# USB_Serial_Quad.net
KiCad netlist of a schematic drawn in Altium Designer
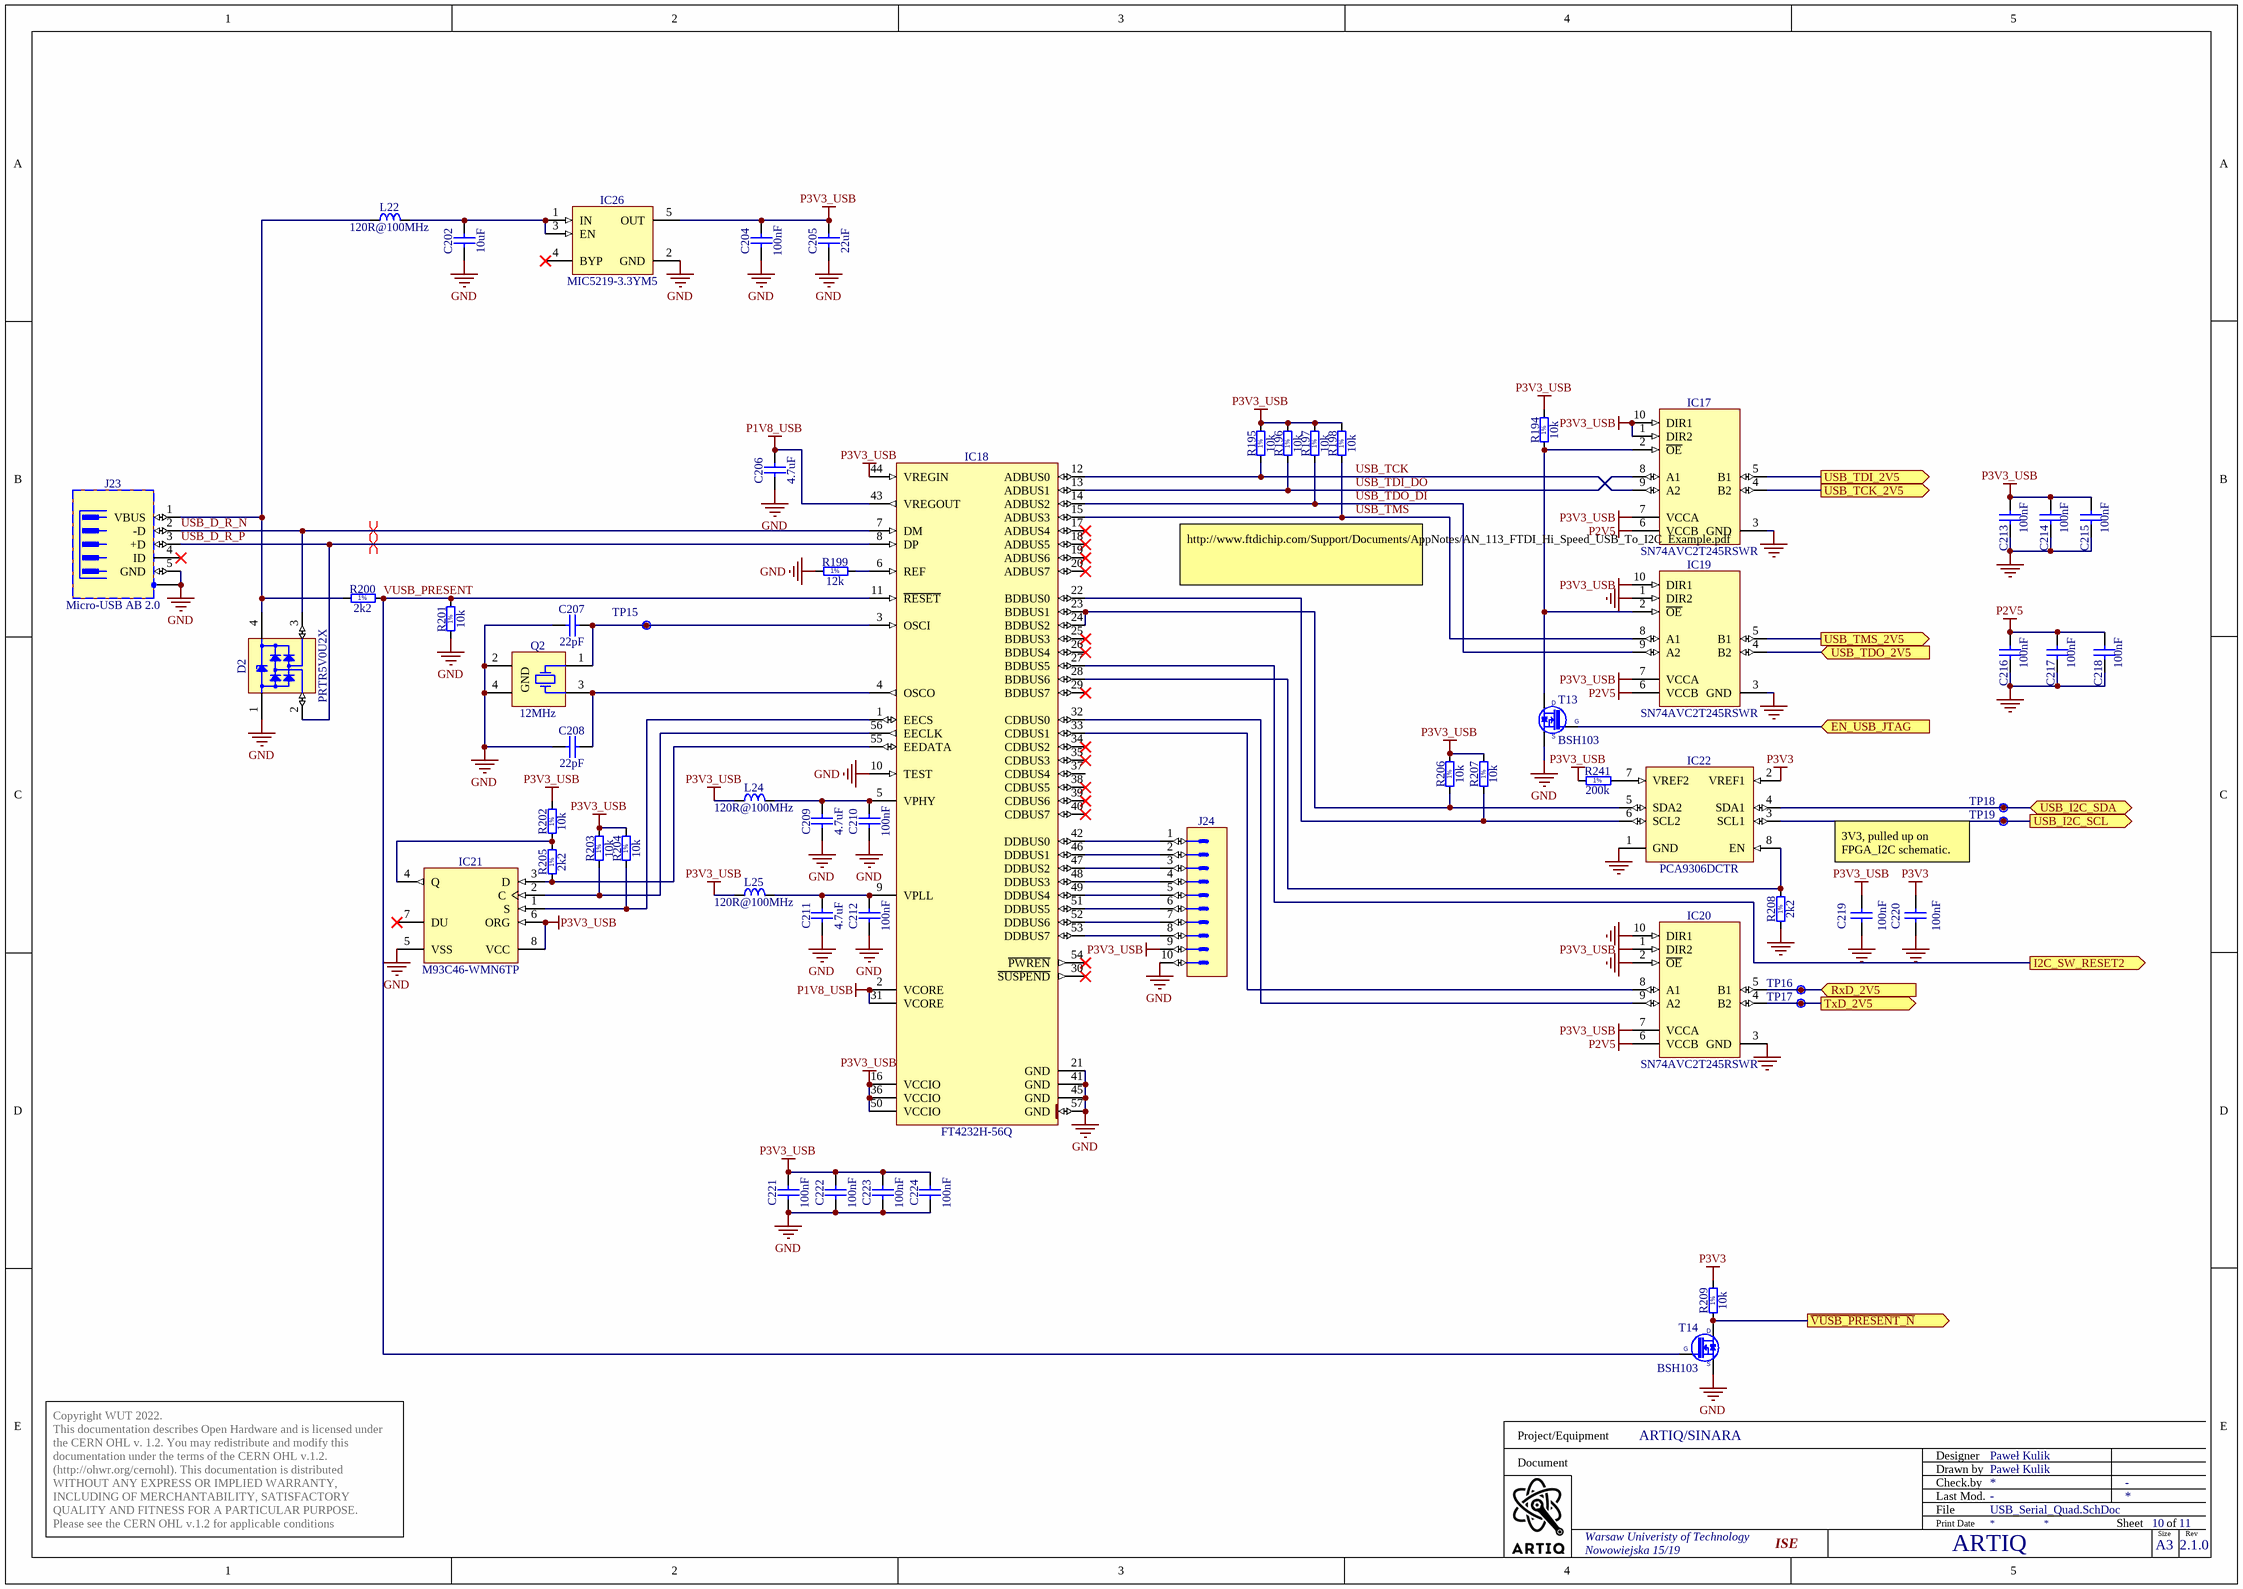
[diagram p0: USB_Serial_Quad.SchDoc]

(export (version "E")
  (design (tool "Eeschema 10.0.6"))
  (components
    (comp (ref "C202")
      (value "10uF")
      (footprint "CAPC1608X87N")
      (description "Non-polarised capacitor")
      (fields
        (field (name "PART NUMBER") "CC0603_10UF_6.3V_20%_X5R")
        (field (name "VOLTAGE") "6.3V")
        (field (name "AUTHOR") "CERN DEM JLC")
      )
      (libsource (lib "Capacitors") (part "Capacitor - non polarized"))
    )
    (comp (ref "C204")
      (value "100nF")
      (footprint "CAPC0603X33N")
      (description "Non-polarised capacitor")
      (fields
        (field (name "PART NUMBER") "CC0201_100NF_6.3V_10%_X5R")
        (field (name "VOLTAGE") "6.3V")
        (field (name "AUTHOR") "CERN DEM JLC")
      )
      (libsource (lib "Capacitors") (part "Capacitor - non polarized"))
    )
    (comp (ref "C205")
      (value "22uF")
      (footprint "CAPC1709X100N")
      (description "Non-polarised capacitor")
      (fields
        (field (name "PART NUMBER") "CC0603_22UF_6.3V_20%_X5R")
        (field (name "VOLTAGE") "6.3V")
        (field (name "AUTHOR") "CERN DEM JLC")
      )
      (libsource (lib "Capacitors") (part "Capacitor - non polarized"))
    )
    (comp (ref "C206")
      (value "4.7uF")
      (footprint "CAPC2012X135N")
      (description "Non-polarised capacitor")
      (fields
        (field (name "PART NUMBER") "CC0805_4.7UF_10V_10%_X5R")
        (field (name "VOLTAGE") "10V")
        (field (name "AUTHOR") "CERN DEM JLC")
      )
      (libsource (lib "Capacitors") (part "Capacitor - non polarized"))
    )
    (comp (ref "C207")
      (value "22pF")
      (footprint "CAPC1005X55N")
      (description "Non-polarised capacitor")
      (fields
        (field (name "PART NUMBER") "CC0402_22PF_50V_5%_C0G")
        (field (name "VOLTAGE") "50V")
        (field (name "AUTHOR") "CERN DEM JLC")
      )
      (libsource (lib "Capacitors") (part "Capacitor - non polarized"))
    )
    (comp (ref "C208")
      (value "22pF")
      (footprint "CAPC1005X55N")
      (description "Non-polarised capacitor")
      (fields
        (field (name "PART NUMBER") "CC0402_22PF_50V_5%_C0G")
        (field (name "VOLTAGE") "50V")
        (field (name "AUTHOR") "CERN DEM JLC")
      )
      (libsource (lib "Capacitors") (part "Capacitor - non polarized"))
    )
    (comp (ref "C209")
      (value "4.7uF")
      (footprint "CAPC2012X135N")
      (description "Non-polarised capacitor")
      (fields
        (field (name "PART NUMBER") "CC0805_4.7UF_10V_10%_X5R")
        (field (name "VOLTAGE") "10V")
        (field (name "AUTHOR") "CERN DEM JLC")
      )
      (libsource (lib "Capacitors") (part "Capacitor - non polarized"))
    )
    (comp (ref "C210")
      (value "100nF")
      (footprint "CAPC0603X33N")
      (description "Non-polarised capacitor")
      (fields
        (field (name "PART NUMBER") "CC0201_100NF_6.3V_10%_X5R")
        (field (name "VOLTAGE") "6.3V")
        (field (name "AUTHOR") "CERN DEM JLC")
      )
      (libsource (lib "Capacitors") (part "Capacitor - non polarized"))
    )
    (comp (ref "C211")
      (value "4.7uF")
      (footprint "CAPC2012X135N")
      (description "Non-polarised capacitor")
      (fields
        (field (name "PART NUMBER") "CC0805_4.7UF_10V_10%_X5R")
        (field (name "VOLTAGE") "10V")
        (field (name "AUTHOR") "CERN DEM JLC")
      )
      (libsource (lib "Capacitors") (part "Capacitor - non polarized"))
    )
    (comp (ref "C212")
      (value "100nF")
      (footprint "CAPC0603X33N")
      (description "Non-polarised capacitor")
      (fields
        (field (name "PART NUMBER") "CC0201_100NF_6.3V_10%_X5R")
        (field (name "VOLTAGE") "6.3V")
        (field (name "AUTHOR") "CERN DEM JLC")
      )
      (libsource (lib "Capacitors") (part "Capacitor - non polarized"))
    )
    (comp (ref "C213")
      (value "100nF")
      (footprint "CAPC0603X33N")
      (description "Non-polarised capacitor")
      (fields
        (field (name "PART NUMBER") "CC0201_100NF_6.3V_10%_X5R")
        (field (name "VOLTAGE") "6.3V")
        (field (name "AUTHOR") "CERN DEM JLC")
      )
      (libsource (lib "Capacitors") (part "Capacitor - non polarized"))
    )
    (comp (ref "C214")
      (value "100nF")
      (footprint "CAPC0603X33N")
      (description "Non-polarised capacitor")
      (fields
        (field (name "PART NUMBER") "CC0201_100NF_6.3V_10%_X5R")
        (field (name "VOLTAGE") "6.3V")
        (field (name "AUTHOR") "CERN DEM JLC")
      )
      (libsource (lib "Capacitors") (part "Capacitor - non polarized"))
    )
    (comp (ref "C215")
      (value "100nF")
      (footprint "CAPC0603X33N")
      (description "Non-polarised capacitor")
      (fields
        (field (name "PART NUMBER") "CC0201_100NF_6.3V_10%_X5R")
        (field (name "VOLTAGE") "6.3V")
        (field (name "AUTHOR") "CERN DEM JLC")
      )
      (libsource (lib "Capacitors") (part "Capacitor - non polarized"))
    )
    (comp (ref "C216")
      (value "100nF")
      (footprint "CAPC0603X33N")
      (description "Non-polarised capacitor")
      (fields
        (field (name "PART NUMBER") "CC0201_100NF_6.3V_10%_X5R")
        (field (name "VOLTAGE") "6.3V")
        (field (name "AUTHOR") "CERN DEM JLC")
      )
      (libsource (lib "Capacitors") (part "Capacitor - non polarized"))
    )
    (comp (ref "C217")
      (value "100nF")
      (footprint "CAPC0603X33N")
      (description "Non-polarised capacitor")
      (fields
        (field (name "PART NUMBER") "CC0201_100NF_6.3V_10%_X5R")
        (field (name "VOLTAGE") "6.3V")
        (field (name "AUTHOR") "CERN DEM JLC")
      )
      (libsource (lib "Capacitors") (part "Capacitor - non polarized"))
    )
    (comp (ref "C218")
      (value "100nF")
      (footprint "CAPC0603X33N")
      (description "Non-polarised capacitor")
      (fields
        (field (name "PART NUMBER") "CC0201_100NF_6.3V_10%_X5R")
        (field (name "VOLTAGE") "6.3V")
        (field (name "AUTHOR") "CERN DEM JLC")
      )
      (libsource (lib "Capacitors") (part "Capacitor - non polarized"))
    )
    (comp (ref "C219")
      (value "100nF")
      (footprint "CAPC0603X33N")
      (description "Non-polarised capacitor")
      (fields
        (field (name "PART NUMBER") "CC0201_100NF_6.3V_10%_X5R")
        (field (name "VOLTAGE") "6.3V")
        (field (name "AUTHOR") "CERN DEM JLC")
      )
      (libsource (lib "Capacitors") (part "Capacitor - non polarized"))
    )
    (comp (ref "C220")
      (value "100nF")
      (footprint "CAPC0603X33N")
      (description "Non-polarised capacitor")
      (fields
        (field (name "PART NUMBER") "CC0201_100NF_6.3V_10%_X5R")
        (field (name "VOLTAGE") "6.3V")
        (field (name "AUTHOR") "CERN DEM JLC")
      )
      (libsource (lib "Capacitors") (part "Capacitor - non polarized"))
    )
    (comp (ref "C221")
      (value "100nF")
      (footprint "CAPC0603X33N")
      (description "Non-polarised capacitor")
      (fields
        (field (name "PART NUMBER") "CC0201_100NF_6.3V_10%_X5R")
        (field (name "VOLTAGE") "6.3V")
        (field (name "AUTHOR") "CERN DEM JLC")
      )
      (libsource (lib "Capacitors") (part "Capacitor - non polarized"))
    )
    (comp (ref "C222")
      (value "100nF")
      (footprint "CAPC0603X33N")
      (description "Non-polarised capacitor")
      (fields
        (field (name "PART NUMBER") "CC0201_100NF_6.3V_10%_X5R")
        (field (name "VOLTAGE") "6.3V")
        (field (name "AUTHOR") "CERN DEM JLC")
      )
      (libsource (lib "Capacitors") (part "Capacitor - non polarized"))
    )
    (comp (ref "C223")
      (value "100nF")
      (footprint "CAPC0603X33N")
      (description "Non-polarised capacitor")
      (fields
        (field (name "PART NUMBER") "CC0201_100NF_6.3V_10%_X5R")
        (field (name "VOLTAGE") "6.3V")
        (field (name "AUTHOR") "CERN DEM JLC")
      )
      (libsource (lib "Capacitors") (part "Capacitor - non polarized"))
    )
    (comp (ref "C224")
      (value "100nF")
      (footprint "CAPC0603X33N")
      (description "Non-polarised capacitor")
      (fields
        (field (name "PART NUMBER") "CC0201_100NF_6.3V_10%_X5R")
        (field (name "VOLTAGE") "6.3V")
        (field (name "AUTHOR") "CERN DEM JLC")
      )
      (libsource (lib "Capacitors") (part "Capacitor - non polarized"))
    )
    (comp (ref "D2")
      (value "PRTR5V0U2X")
      (footprint "SOT190P230X110-4N")
      (description "Ultra Low Capacitance Double Rail-to-Rail ESD Protection Diode")
      (fields
        (field (name "VOLTAGE") "5.5V")
        (field (name "MANUFACTURER") "NXP SEMICONDUCTORS")
        (field (name "AUTHOR") "CERN DEM JLC")
      )
      (libsource (lib "ICs And Semiconductors") (part "PRTR5V0U2X"))
    )
    (comp (ref "IC17")
      (value "SN74AVC2T245RSWR")
      (footprint "QFN40P140X180X55-10N")
      (description "Dual-Bit Dual-Supply Bus Transceiver With Configurable Voltage Translation and 3-State Outputs")
      (fields (field (name "MANUFACTURER") "TEXAS INSTRUMENTS") (field (name "AUTHOR") "CERN DEM JLC"))
      (libsource (lib "ICs And Semiconductors") (part "742T245"))
    )
    (comp (ref "IC18")
      (value "FT4232H-56Q")
      (footprint "QFN50P800X800X100-57N-S620")
      (description "Quad High Speed USB to Multipurpose UART/MPSSE IC")
      (fields
        (field (name "MANUFACTURER") "FUTURE TECHNOLOGY DEVICES INTERNATIONAL (FTDI)")
        (field (name "AUTHOR") "CERN DEM JLC")
      )
      (libsource (lib "ICs And Semiconductors") (part "FT4232H-56Q"))
    )
    (comp (ref "IC19")
      (value "SN74AVC2T245RSWR")
      (footprint "QFN40P140X180X55-10N")
      (description "Dual-Bit Dual-Supply Bus Transceiver With Configurable Voltage Translation and 3-State Outputs")
      (fields (field (name "MANUFACTURER") "TEXAS INSTRUMENTS") (field (name "AUTHOR") "CERN DEM JLC"))
      (libsource (lib "ICs And Semiconductors") (part "742T245"))
    )
    (comp (ref "IC20")
      (value "SN74AVC2T245RSWR")
      (footprint "QFN40P140X180X55-10N")
      (description "Dual-Bit Dual-Supply Bus Transceiver With Configurable Voltage Translation and 3-State Outputs")
      (fields (field (name "MANUFACTURER") "TEXAS INSTRUMENTS") (field (name "AUTHOR") "CERN DEM JLC"))
      (libsource (lib "ICs And Semiconductors") (part "742T245"))
    )
    (comp (ref "IC21")
      (value "M93C46-WMN6TP")
      (footprint "SOIC127P600X175-8N")
      (description "2.5 to 5.5 V, 1Kb (128x8) Serial Microwire Bus EEPROM")
      (fields (field (name "MANUFACTURER") "ST MICROELECTRONICS") (field (name "AUTHOR") "CERN DEM JLC"))
      (libsource (lib "ICs And Semiconductors") (part "M93C46-WMN6TP"))
    )
    (comp (ref "IC22")
      (value "PCA9306DCTR")
      (footprint "SOP65P400X130-8N")
      (description "Dual Bidirectional I2C Bus And SMBus Voltage-Level Translator")
      (fields (field (name "MANUFACTURER") "TEXAS INSTRUMENTS") (field (name "AUTHOR") "CERN DEM JLC"))
      (libsource (lib "ICs And Semiconductors") (part "PCA9306D"))
    )
    (comp (ref "IC26")
      (value "MIC5219-3.3YM5")
      (footprint "SOT95P280X145-5N")
      (description "500mA Peak Output LDO Regulator")
      (fields (field (name "MANUFACTURER") "MICROCHIP TECHNOLOGY") (field (name "AUTHOR") "CERN DEM WB"))
      (libsource (lib "ICs And Semiconductors") (part "MIC5219-X.XYM5"))
    )
    (comp (ref "J23")
      (value "Micro-USB AB 2.0")
      (footprint "HIROSE_ZX62RD-AB-5P8")
      (description "5 Pin + 1 Shield USB Receptacle")
      (fields
        (field (name "PART NUMBER") "HIROSE_ZX62RD-AB-5P8")
        (field (name "MANUFACTURER") "HIROSE (HRS)")
        (field (name "AUTHOR") "CERN DEM JLC")
      )
      (libsource (lib "Connectors") (part "Connector USB 5 Pin + 1Shield"))
    )
    (comp (ref "J24")
      (value "Header 10")
      (footprint "SAMTEC_TSW-105-07-L-D-LL")
      (description "Connector 10 Male")
      (fields
        (field (name "PART NUMBER") "SAMTEC_TSW-105-07-L-D-LL")
        (field (name "MANUFACTURER") "SAMTEC")
        (field (name "AUTHOR") "CERN DEM JLC")
      )
      (libsource (lib "Connectors") (part "Connector 10 Male"))
    )
    (comp (ref "L22")
      (value "120R@100MHz")
      (footprint "INDC1608X65N")
      (description "Inductor")
      (fields
        (field (name "PART NUMBER") "IND0603_MURATA_BLM18SG121TN1D")
        (field (name "POWER") "3A")
        (field (name "AUTHOR") "CERN DEM JLC")
      )
      (libsource (lib "Inductors & Transformers") (part "Inductor"))
    )
    (comp (ref "L24")
      (value "120R@100MHz")
      (footprint "INDC1608X65N")
      (description "Inductor")
      (fields
        (field (name "PART NUMBER") "IND0603_MURATA_BLM18SG121TN1D")
        (field (name "POWER") "3A")
        (field (name "AUTHOR") "CERN DEM JLC")
      )
      (libsource (lib "Inductors & Transformers") (part "Inductor"))
    )
    (comp (ref "L25")
      (value "120R@100MHz")
      (footprint "INDC1608X65N")
      (description "Inductor")
      (fields
        (field (name "PART NUMBER") "IND0603_MURATA_BLM18SG121TN1D")
        (field (name "POWER") "3A")
        (field (name "AUTHOR") "CERN DEM JLC")
      )
      (libsource (lib "Inductors & Transformers") (part "Inductor"))
    )
    (comp (ref "Q2")
      (value "12MHz")
      (footprint "XTAL_TXC_7M")
      (description "Crystal 4 pins 1=XTAL Control 2=GND3=XTAL 4=GND")
      (fields
        (field (name "PART NUMBER") "XTAL_12MHZ_TXC_7M-12.000MAAJ-T")
        (field (name "MANUFACTURER") "TXC CORPORATION")
        (field (name "AUTHOR") "CERN DEM JLC")
      )
      (libsource (lib "ICs And Semiconductors") (part "Quartz Crystal 1X 2GND 3X 4GND"))
    )
    (comp (ref "R194")
      (value "10k")
      (footprint "RESC1005X40N")
      (description "Resistor - 1%")
      (fields
        (field (name "PART NUMBER") "R0402_10K_1%_0.0625W_100PPM")
        (field (name "POWER") "0.0625W")
        (field (name "AUTHOR") "CERN DEM JLC")
      )
      (libsource (lib "Resistors") (part "Resistor - 1%"))
    )
    (comp (ref "R195")
      (value "10k")
      (footprint "RESC1005X40N")
      (description "Resistor - 1%")
      (fields
        (field (name "PART NUMBER") "R0402_10K_1%_0.0625W_100PPM")
        (field (name "POWER") "0.0625W")
        (field (name "AUTHOR") "CERN DEM JLC")
      )
      (libsource (lib "Resistors") (part "Resistor - 1%"))
    )
    (comp (ref "R196")
      (value "10k")
      (footprint "RESC1005X40N")
      (description "Resistor - 1%")
      (fields
        (field (name "PART NUMBER") "R0402_10K_1%_0.0625W_100PPM")
        (field (name "POWER") "0.0625W")
        (field (name "AUTHOR") "CERN DEM JLC")
      )
      (libsource (lib "Resistors") (part "Resistor - 1%"))
    )
    (comp (ref "R197")
      (value "10k")
      (footprint "RESC1005X40N")
      (description "Resistor - 1%")
      (fields
        (field (name "PART NUMBER") "R0402_10K_1%_0.0625W_100PPM")
        (field (name "POWER") "0.0625W")
        (field (name "AUTHOR") "CERN DEM JLC")
      )
      (libsource (lib "Resistors") (part "Resistor - 1%"))
    )
    (comp (ref "R198")
      (value "10k")
      (footprint "RESC1005X40N")
      (description "Resistor - 1%")
      (fields
        (field (name "PART NUMBER") "R0402_10K_1%_0.0625W_100PPM")
        (field (name "POWER") "0.0625W")
        (field (name "AUTHOR") "CERN DEM JLC")
      )
      (libsource (lib "Resistors") (part "Resistor - 1%"))
    )
    (comp (ref "R199")
      (value "12k")
      (footprint "RESC1005X40N")
      (description "Resistor - 1%")
      (fields
        (field (name "PART NUMBER") "R0402_12K_1%_0.0625W_100PPM")
        (field (name "POWER") "0.0625W")
        (field (name "AUTHOR") "CERN DEM JLC")
      )
      (libsource (lib "Resistors") (part "Resistor - 1%"))
    )
    (comp (ref "R200")
      (value "2k2")
      (footprint "RESC1005X40N")
      (description "Resistor - 1%")
      (fields
        (field (name "PART NUMBER") "R0402_2K2_1%_0.0625W_100PPM")
        (field (name "POWER") "0.0625W")
        (field (name "AUTHOR") "CERN DEM JLC")
      )
      (libsource (lib "Resistors") (part "Resistor - 1%"))
    )
    (comp (ref "R201")
      (value "10k")
      (footprint "RESC1005X40N")
      (description "Resistor - 1%")
      (fields
        (field (name "PART NUMBER") "R0402_10K_1%_0.0625W_100PPM")
        (field (name "POWER") "0.0625W")
        (field (name "AUTHOR") "CERN DEM JLC")
      )
      (libsource (lib "Resistors") (part "Resistor - 1%"))
    )
    (comp (ref "R202")
      (value "10k")
      (footprint "RESC1005X40N")
      (description "Resistor - 1%")
      (fields
        (field (name "PART NUMBER") "R0402_10K_1%_0.0625W_100PPM")
        (field (name "POWER") "0.0625W")
        (field (name "AUTHOR") "CERN DEM JLC")
      )
      (libsource (lib "Resistors") (part "Resistor - 1%"))
    )
    (comp (ref "R203")
      (value "10k")
      (footprint "RESC1005X40N")
      (description "Resistor - 1%")
      (fields
        (field (name "PART NUMBER") "R0402_10K_1%_0.0625W_100PPM")
        (field (name "POWER") "0.0625W")
        (field (name "AUTHOR") "CERN DEM JLC")
      )
      (libsource (lib "Resistors") (part "Resistor - 1%"))
    )
    (comp (ref "R204")
      (value "10k")
      (footprint "RESC1005X40N")
      (description "Resistor - 1%")
      (fields
        (field (name "PART NUMBER") "R0402_10K_1%_0.0625W_100PPM")
        (field (name "POWER") "0.0625W")
        (field (name "AUTHOR") "CERN DEM JLC")
      )
      (libsource (lib "Resistors") (part "Resistor - 1%"))
    )
    (comp (ref "R205")
      (value "2k2")
      (footprint "RESC1005X40N")
      (description "Resistor - 1%")
      (fields
        (field (name "PART NUMBER") "R0402_2K2_1%_0.0625W_100PPM")
        (field (name "POWER") "0.0625W")
        (field (name "AUTHOR") "CERN DEM JLC")
      )
      (libsource (lib "Resistors") (part "Resistor - 1%"))
    )
    (comp (ref "R206")
      (value "10k")
      (footprint "RESC1005X40N")
      (description "Resistor - 1%")
      (fields
        (field (name "PART NUMBER") "R0402_10K_1%_0.0625W_100PPM")
        (field (name "POWER") "0.0625W")
        (field (name "AUTHOR") "CERN DEM JLC")
      )
      (libsource (lib "Resistors") (part "Resistor - 1%"))
    )
    (comp (ref "R207")
      (value "10k")
      (footprint "RESC1005X40N")
      (description "Resistor - 1%")
      (fields
        (field (name "PART NUMBER") "R0402_10K_1%_0.0625W_100PPM")
        (field (name "POWER") "0.0625W")
        (field (name "AUTHOR") "CERN DEM JLC")
      )
      (libsource (lib "Resistors") (part "Resistor - 1%"))
    )
    (comp (ref "R208")
      (value "2k2")
      (footprint "RESC1005X40N")
      (description "Resistor - 1%")
      (fields
        (field (name "PART NUMBER") "R0402_2K2_1%_0.0625W_100PPM")
        (field (name "POWER") "0.0625W")
        (field (name "AUTHOR") "CERN DEM JLC")
      )
      (libsource (lib "Resistors") (part "Resistor - 1%"))
    )
    (comp (ref "R209")
      (value "10k")
      (footprint "RESC1005X40N")
      (description "Resistor - 1%")
      (fields
        (field (name "PART NUMBER") "R0402_10K_1%_0.0625W_100PPM")
        (field (name "POWER") "0.0625W")
        (field (name "AUTHOR") "CERN DEM JLC")
      )
      (libsource (lib "Resistors") (part "Resistor - 1%"))
    )
    (comp (ref "R241")
      (value "200k")
      (footprint "RESC1005X40N")
      (description "Resistor - 1%")
      (fields
        (field (name "PART NUMBER") "R0402_200K_1%_0.0625W_100PPM")
        (field (name "POWER") "0.0625W")
        (field (name "AUTHOR") "CERN DEM JLC")
      )
      (libsource (lib "Resistors") (part "Resistor - 1%"))
    )
    (comp (ref "T13")
      (value "BSH103")
      (footprint "SOT95P230X110-3N")
      (description "N-CHANNEL MOSFET WITH DIODE")
      (fields (field (name "MANUFACTURER") "NEXPERIA") (field (name "AUTHOR") "CERN DEM JLC"))
      (libsource (lib "ICs And Semiconductors") (part "N-MOSFET-D 1G 2S 3D"))
    )
    (comp (ref "T14")
      (value "BSH103")
      (footprint "SOT95P230X110-3N")
      (description "N-CHANNEL MOSFET WITH DIODE")
      (fields (field (name "MANUFACTURER") "NEXPERIA") (field (name "AUTHOR") "CERN DEM JLC"))
      (libsource (lib "") (part "N-MOSFET-D 1G 2S 3D_1"))
    )
    (comp (ref "TP15")
      (value "Q2")
      (footprint "TPS127")
      (description "Test Point")
      (fields (field (name "PART NUMBER") "SMD_PAD_1.27X1.27MM") (field (name "AUTHOR") "CERN DEM JLC"))
      (libsource (lib "Eletro-mechanical") (part "Test Point"))
    )
    (comp (ref "TP16")
      (value "RxD")
      (footprint "TPS127")
      (description "Test Point")
      (fields (field (name "PART NUMBER") "SMD_PAD_1.27X1.27MM") (field (name "AUTHOR") "CERN DEM JLC"))
      (libsource (lib "Eletro-mechanical") (part "Test Point"))
    )
    (comp (ref "TP17")
      (value "TxD")
      (footprint "TPS127")
      (description "Test Point")
      (fields (field (name "PART NUMBER") "SMD_PAD_1.27X1.27MM") (field (name "AUTHOR") "CERN DEM JLC"))
      (libsource (lib "Eletro-mechanical") (part "Test Point"))
    )
    (comp (ref "TP18")
      (value "USB I2C SDA")
      (footprint "TPS127")
      (description "Test Point")
      (fields (field (name "PART NUMBER") "SMD_PAD_1.27X1.27MM") (field (name "AUTHOR") "CERN DEM JLC"))
      (libsource (lib "Eletro-mechanical") (part "Test Point"))
    )
    (comp (ref "TP19")
      (value "USB I2C SCL")
      (footprint "TPS127")
      (description "Test Point")
      (fields (field (name "PART NUMBER") "SMD_PAD_1.27X1.27MM") (field (name "AUTHOR") "CERN DEM JLC"))
      (libsource (lib "Eletro-mechanical") (part "Test Point"))
    )
  )
  (nets
    (net (code "1") (name "/EN_USB_JTAG") (class "Default")
      (node (ref "T13") (pin "1") (pinfunction "G_1") (pintype "passive"))
    )
    (net (code "2") (name "/I2C_SW_RESET2") (class "Default")
      (node (ref "IC18") (pin "27") (pinfunction "BDBUS5_27") (pintype "bidirectional"))
    )
    (net (code "3") (name "/RxD_2V5") (class "Default")
      (node (ref "IC20") (pin "5") (pinfunction "B1_5") (pintype "bidirectional"))
      (node (ref "TP16") (pin "1") (pinfunction "1_1") (pintype "bidirectional"))
    )
    (net (code "4") (name "/TxD_2V5") (class "Default")
      (node (ref "IC20") (pin "4") (pinfunction "B2_4") (pintype "bidirectional"))
      (node (ref "TP17") (pin "1") (pinfunction "1_1") (pintype "bidirectional"))
    )
    (net (code "5") (name "/USB_D_R_N") (class "Default")
      (node (ref "D2") (pin "3") (pinfunction "I/O2_3") (pintype "bidirectional"))
      (node (ref "IC18") (pin "7") (pinfunction "DM_7") (pintype "input"))
      (node (ref "J23") (pin "2") (pinfunction "-D_2") (pintype "bidirectional"))
    )
    (net (code "6") (name "/USB_D_R_P") (class "Default")
      (node (ref "D2") (pin "2") (pinfunction "I/O1_2") (pintype "bidirectional"))
      (node (ref "IC18") (pin "8") (pinfunction "DP_8") (pintype "input"))
      (node (ref "J23") (pin "3") (pinfunction "+D_3") (pintype "bidirectional"))
    )
    (net (code "7") (name "/USB_I2C_SCL") (class "Default")
      (node (ref "IC22") (pin "3") (pinfunction "SCL1_3") (pintype "bidirectional"))
      (node (ref "TP19") (pin "1") (pinfunction "1_1") (pintype "bidirectional"))
    )
    (net (code "8") (name "/USB_I2C_SDA") (class "Default")
      (node (ref "IC22") (pin "4") (pinfunction "SDA1_4") (pintype "bidirectional"))
      (node (ref "TP18") (pin "1") (pinfunction "1_1") (pintype "bidirectional"))
    )
    (net (code "9") (name "/USB_TCK") (class "Default")
      (node (ref "IC17") (pin "9") (pinfunction "A2_9") (pintype "bidirectional"))
      (node (ref "IC18") (pin "12") (pinfunction "ADBUS0_12") (pintype "bidirectional"))
      (node (ref "R195") (pin "1") (pinfunction "1_1") (pintype "passive"))
    )
    (net (code "10") (name "/USB_TCK_2V5") (class "Default")
      (node (ref "IC17") (pin "4") (pinfunction "B2_4") (pintype "bidirectional"))
    )
    (net (code "11") (name "/USB_TDI_2V5") (class "Default")
      (node (ref "IC17") (pin "5") (pinfunction "B1_5") (pintype "bidirectional"))
    )
    (net (code "12") (name "/USB_TDI_DO") (class "Default")
      (node (ref "IC17") (pin "8") (pinfunction "A1_8") (pintype "bidirectional"))
      (node (ref "IC18") (pin "13") (pinfunction "ADBUS1_13") (pintype "bidirectional"))
      (node (ref "R196") (pin "1") (pinfunction "1_1") (pintype "passive"))
    )
    (net (code "13") (name "/USB_TDO_2V5") (class "Default")
      (node (ref "IC19") (pin "4") (pinfunction "B2_4") (pintype "bidirectional"))
    )
    (net (code "14") (name "/USB_TDO_DI") (class "Default")
      (node (ref "IC18") (pin "14") (pinfunction "ADBUS2_14") (pintype "bidirectional"))
      (node (ref "IC19") (pin "9") (pinfunction "A2_9") (pintype "bidirectional"))
      (node (ref "R197") (pin "1") (pinfunction "1_1") (pintype "passive"))
    )
    (net (code "15") (name "/USB_TMS") (class "Default")
      (node (ref "IC18") (pin "15") (pinfunction "ADBUS3_15") (pintype "bidirectional"))
      (node (ref "IC19") (pin "8") (pinfunction "A1_8") (pintype "bidirectional"))
      (node (ref "R198") (pin "1") (pinfunction "1_1") (pintype "passive"))
    )
    (net (code "16") (name "/USB_TMS_2V5") (class "Default")
      (node (ref "IC19") (pin "5") (pinfunction "B1_5") (pintype "bidirectional"))
    )
    (net (code "17") (name "/VUSB_PRESENT") (class "Default")
      (node (ref "IC18") (pin "11") (pinfunction "~{RESET}_11") (pintype "input"))
      (node (ref "R200") (pin "2") (pinfunction "2_2") (pintype "passive"))
      (node (ref "R201") (pin "2") (pinfunction "2_2") (pintype "passive"))
      (node (ref "T14") (pin "1") (pinfunction "G_1") (pintype "passive"))
    )
    (net (code "18") (name "/VUSB_PRESENT_N") (class "Default")
      (node (ref "R209") (pin "1") (pinfunction "1_1") (pintype "passive"))
      (node (ref "T14") (pin "3") (pinfunction "D_3") (pintype "passive"))
    )
    (net (code "19") (name "GND") (class "Default")
      (node (ref "C202") (pin "1") (pinfunction "1_1") (pintype "passive"))
      (node (ref "C204") (pin "1") (pinfunction "1_1") (pintype "passive"))
      (node (ref "C205") (pin "1") (pinfunction "1_1") (pintype "passive"))
      (node (ref "C206") (pin "1") (pinfunction "1_1") (pintype "passive"))
      (node (ref "C207") (pin "1") (pinfunction "1_1") (pintype "passive"))
      (node (ref "C208") (pin "1") (pinfunction "1_1") (pintype "passive"))
      (node (ref "C209") (pin "1") (pinfunction "1_1") (pintype "passive"))
      (node (ref "C210") (pin "1") (pinfunction "1_1") (pintype "passive"))
      (node (ref "C211") (pin "1") (pinfunction "1_1") (pintype "passive"))
      (node (ref "C212") (pin "1") (pinfunction "1_1") (pintype "passive"))
      (node (ref "C213") (pin "1") (pinfunction "1_1") (pintype "passive"))
      (node (ref "C214") (pin "1") (pinfunction "1_1") (pintype "passive"))
      (node (ref "C215") (pin "1") (pinfunction "1_1") (pintype "passive"))
      (node (ref "C216") (pin "1") (pinfunction "1_1") (pintype "passive"))
      (node (ref "C217") (pin "1") (pinfunction "1_1") (pintype "passive"))
      (node (ref "C218") (pin "1") (pinfunction "1_1") (pintype "passive"))
      (node (ref "C219") (pin "1") (pinfunction "1_1") (pintype "passive"))
      (node (ref "C220") (pin "1") (pinfunction "1_1") (pintype "passive"))
      (node (ref "C221") (pin "1") (pinfunction "1_1") (pintype "passive"))
      (node (ref "C222") (pin "1") (pinfunction "1_1") (pintype "passive"))
      (node (ref "C223") (pin "1") (pinfunction "1_1") (pintype "passive"))
      (node (ref "C224") (pin "1") (pinfunction "1_1") (pintype "passive"))
      (node (ref "D2") (pin "1") (pinfunction "GND_1") (pintype "power_in"))
      (node (ref "IC17") (pin "3") (pinfunction "GND_3") (pintype "power_in"))
      (node (ref "IC18") (pin "10") (pinfunction "TEST_10") (pintype "input"))
      (node (ref "IC18") (pin "21") (pinfunction "GND_21") (pintype "power_in"))
      (node (ref "IC18") (pin "41") (pinfunction "GND_41") (pintype "power_in"))
      (node (ref "IC18") (pin "45") (pinfunction "GND_45") (pintype "power_in"))
      (node (ref "IC18") (pin "57") (pinfunction "GND_57") (pintype "bidirectional"))
      (node (ref "IC19") (pin "1") (pinfunction "DIR2_1") (pintype "input"))
      (node (ref "IC19") (pin "3") (pinfunction "GND_3") (pintype "power_in"))
      (node (ref "IC20") (pin "10") (pinfunction "DIR1_10") (pintype "input"))
      (node (ref "IC20") (pin "2") (pinfunction "~{OE}_2") (pintype "input"))
      (node (ref "IC20") (pin "3") (pinfunction "GND_3") (pintype "power_in"))
      (node (ref "IC21") (pin "5") (pinfunction "VSS_5") (pintype "power_in"))
      (node (ref "IC22") (pin "1") (pinfunction "GND_1") (pintype "power_in"))
      (node (ref "IC26") (pin "2") (pinfunction "GND_2") (pintype "power_in"))
      (node (ref "J23") (pin "5") (pinfunction "GND_5") (pintype "bidirectional"))
      (node (ref "J23") (pin "6") (pinfunction "SH_6") (pintype "power_in"))
      (node (ref "J24") (pin "10") (pinfunction "10_10") (pintype "bidirectional"))
      (node (ref "Q2") (pin "2") (pinfunction "GND_2") (pintype "power_in"))
      (node (ref "Q2") (pin "4") (pinfunction "GND_4") (pintype "power_in"))
      (node (ref "R199") (pin "1") (pinfunction "1_1") (pintype "passive"))
      (node (ref "R201") (pin "1") (pinfunction "1_1") (pintype "passive"))
      (node (ref "R208") (pin "1") (pinfunction "1_1") (pintype "passive"))
      (node (ref "T13") (pin "2") (pinfunction "S_2") (pintype "passive"))
      (node (ref "T14") (pin "2") (pinfunction "S_2") (pintype "passive"))
    )
    (net (code "20") (name "Net-(D2-VCC)") (class "Default")
      (node (ref "D2") (pin "4") (pinfunction "VCC_4") (pintype "power_in"))
      (node (ref "J23") (pin "1") (pinfunction "VBUS_1") (pintype "bidirectional"))
      (node (ref "L22") (pin "1") (pinfunction "1_1") (pintype "passive"))
      (node (ref "R200") (pin "1") (pinfunction "1_1") (pintype "passive"))
    )
    (net (code "21") (name "Net-(IC17-~{OE})") (class "Default")
      (node (ref "IC17") (pin "2") (pinfunction "~{OE}_2") (pintype "input"))
      (node (ref "IC19") (pin "2") (pinfunction "~{OE}_2") (pintype "input"))
      (node (ref "R194") (pin "1") (pinfunction "1_1") (pintype "passive"))
      (node (ref "T13") (pin "3") (pinfunction "D_3") (pintype "passive"))
    )
    (net (code "22") (name "Net-(IC18-BDBUS0)") (class "Default")
      (node (ref "IC18") (pin "22") (pinfunction "BDBUS0_22") (pintype "bidirectional"))
      (node (ref "IC22") (pin "6") (pinfunction "SCL2_6") (pintype "bidirectional"))
      (node (ref "R207") (pin "1") (pinfunction "1_1") (pintype "passive"))
    )
    (net (code "23") (name "Net-(IC18-BDBUS1)") (class "Default")
      (node (ref "IC18") (pin "23") (pinfunction "BDBUS1_23") (pintype "bidirectional"))
      (node (ref "IC18") (pin "24") (pinfunction "BDBUS2_24") (pintype "bidirectional"))
      (node (ref "IC22") (pin "5") (pinfunction "SDA2_5") (pintype "bidirectional"))
      (node (ref "R206") (pin "1") (pinfunction "1_1") (pintype "passive"))
    )
    (net (code "24") (name "Net-(IC18-BDBUS6)") (class "Default")
      (node (ref "IC18") (pin "28") (pinfunction "BDBUS6_28") (pintype "bidirectional"))
      (node (ref "IC22") (pin "8") (pinfunction "EN_8") (pintype "input"))
      (node (ref "R208") (pin "2") (pinfunction "2_2") (pintype "passive"))
    )
    (net (code "25") (name "Net-(IC18-CDBUS0)") (class "Default")
      (node (ref "IC18") (pin "32") (pinfunction "CDBUS0_32") (pintype "bidirectional"))
      (node (ref "IC20") (pin "9") (pinfunction "A2_9") (pintype "bidirectional"))
    )
    (net (code "26") (name "Net-(IC18-CDBUS1)") (class "Default")
      (node (ref "IC18") (pin "33") (pinfunction "CDBUS1_33") (pintype "bidirectional"))
      (node (ref "IC20") (pin "8") (pinfunction "A1_8") (pintype "bidirectional"))
    )
    (net (code "27") (name "Net-(IC18-DDBUS0)") (class "Default")
      (node (ref "IC18") (pin "42") (pinfunction "DDBUS0_42") (pintype "bidirectional"))
      (node (ref "J24") (pin "1") (pinfunction "1_1") (pintype "bidirectional"))
    )
    (net (code "28") (name "Net-(IC18-DDBUS1)") (class "Default")
      (node (ref "IC18") (pin "46") (pinfunction "DDBUS1_46") (pintype "bidirectional"))
      (node (ref "J24") (pin "2") (pinfunction "2_2") (pintype "bidirectional"))
    )
    (net (code "29") (name "Net-(IC18-DDBUS2)") (class "Default")
      (node (ref "IC18") (pin "47") (pinfunction "DDBUS2_47") (pintype "bidirectional"))
      (node (ref "J24") (pin "3") (pinfunction "3_3") (pintype "bidirectional"))
    )
    (net (code "30") (name "Net-(IC18-DDBUS3)") (class "Default")
      (node (ref "IC18") (pin "48") (pinfunction "DDBUS3_48") (pintype "bidirectional"))
      (node (ref "J24") (pin "4") (pinfunction "4_4") (pintype "bidirectional"))
    )
    (net (code "31") (name "Net-(IC18-DDBUS4)") (class "Default")
      (node (ref "IC18") (pin "49") (pinfunction "DDBUS4_49") (pintype "bidirectional"))
      (node (ref "J24") (pin "5") (pinfunction "5_5") (pintype "bidirectional"))
    )
    (net (code "32") (name "Net-(IC18-DDBUS5)") (class "Default")
      (node (ref "IC18") (pin "51") (pinfunction "DDBUS5_51") (pintype "bidirectional"))
      (node (ref "J24") (pin "6") (pinfunction "6_6") (pintype "bidirectional"))
    )
    (net (code "33") (name "Net-(IC18-DDBUS6)") (class "Default")
      (node (ref "IC18") (pin "52") (pinfunction "DDBUS6_52") (pintype "bidirectional"))
      (node (ref "J24") (pin "7") (pinfunction "7_7") (pintype "bidirectional"))
    )
    (net (code "34") (name "Net-(IC18-DDBUS7)") (class "Default")
      (node (ref "IC18") (pin "53") (pinfunction "DDBUS7_53") (pintype "bidirectional"))
      (node (ref "J24") (pin "8") (pinfunction "8_8") (pintype "bidirectional"))
    )
    (net (code "35") (name "Net-(IC18-EECLK)") (class "Default")
      (node (ref "IC18") (pin "56") (pinfunction "EECLK_56") (pintype "output"))
      (node (ref "IC21") (pin "2") (pinfunction "C_2") (pintype "input"))
      (node (ref "R203") (pin "1") (pinfunction "1_1") (pintype "passive"))
    )
    (net (code "36") (name "Net-(IC18-EECS)") (class "Default")
      (node (ref "IC18") (pin "1") (pinfunction "EECS_1") (pintype "bidirectional"))
      (node (ref "IC21") (pin "1") (pinfunction "S_1") (pintype "input"))
      (node (ref "R204") (pin "1") (pinfunction "1_1") (pintype "passive"))
    )
    (net (code "37") (name "Net-(IC18-EEDATA)") (class "Default")
      (node (ref "IC18") (pin "55") (pinfunction "EEDATA_55") (pintype "bidirectional"))
      (node (ref "IC21") (pin "3") (pinfunction "D_3") (pintype "input"))
      (node (ref "R205") (pin "2") (pinfunction "2_2") (pintype "passive"))
    )
    (net (code "38") (name "Net-(IC18-OSCI)") (class "Default")
      (node (ref "C207") (pin "2") (pinfunction "2_2") (pintype "passive"))
      (node (ref "IC18") (pin "3") (pinfunction "OSCI_3") (pintype "input"))
      (node (ref "Q2") (pin "1") (pinfunction "X_1") (pintype "passive"))
      (node (ref "TP15") (pin "1") (pinfunction "1_1") (pintype "bidirectional"))
    )
    (net (code "39") (name "Net-(IC18-OSCO)") (class "Default")
      (node (ref "C208") (pin "2") (pinfunction "2_2") (pintype "passive"))
      (node (ref "IC18") (pin "4") (pinfunction "OSCO_4") (pintype "output"))
      (node (ref "Q2") (pin "3") (pinfunction "X_3") (pintype "passive"))
    )
    (net (code "40") (name "Net-(IC18-REF)") (class "Default")
      (node (ref "IC18") (pin "6") (pinfunction "REF_6") (pintype "input"))
      (node (ref "R199") (pin "2") (pinfunction "2_2") (pintype "passive"))
    )
    (net (code "41") (name "Net-(IC18-VPHY)") (class "Default")
      (node (ref "C209") (pin "2") (pinfunction "2_2") (pintype "passive"))
      (node (ref "C210") (pin "2") (pinfunction "2_2") (pintype "passive"))
      (node (ref "IC18") (pin "5") (pinfunction "VPHY_5") (pintype "power_in"))
      (node (ref "L24") (pin "2") (pinfunction "2_2") (pintype "passive"))
    )
    (net (code "42") (name "Net-(IC18-VPLL)") (class "Default")
      (node (ref "C211") (pin "2") (pinfunction "2_2") (pintype "passive"))
      (node (ref "C212") (pin "2") (pinfunction "2_2") (pintype "passive"))
      (node (ref "IC18") (pin "9") (pinfunction "VPLL_9") (pintype "power_in"))
      (node (ref "L25") (pin "2") (pinfunction "2_2") (pintype "passive"))
    )
    (net (code "43") (name "Net-(IC21-Q)") (class "Default")
      (node (ref "IC21") (pin "4") (pinfunction "Q_4") (pintype "output"))
      (node (ref "R202") (pin "1") (pinfunction "1_1") (pintype "passive"))
      (node (ref "R205") (pin "1") (pinfunction "1_1") (pintype "passive"))
    )
    (net (code "44") (name "Net-(IC22-VREF2)") (class "Default")
      (node (ref "IC22") (pin "7") (pinfunction "VREF2_7") (pintype "input"))
      (node (ref "R241") (pin "2") (pinfunction "2_2") (pintype "passive"))
    )
    (net (code "45") (name "Net-(IC26-EN)") (class "Default")
      (node (ref "C202") (pin "2") (pinfunction "2_2") (pintype "passive"))
      (node (ref "IC26") (pin "1") (pinfunction "IN_1") (pintype "input"))
      (node (ref "IC26") (pin "3") (pinfunction "EN_3") (pintype "input"))
      (node (ref "L22") (pin "2") (pinfunction "2_2") (pintype "passive"))
    )
    (net (code "46") (name "P1V8_USB") (class "Default")
      (node (ref "C206") (pin "2") (pinfunction "2_2") (pintype "passive"))
      (node (ref "IC18") (pin "2") (pinfunction "VCORE_2") (pintype "power_in"))
      (node (ref "IC18") (pin "31") (pinfunction "VCORE_31") (pintype "power_in"))
      (node (ref "IC18") (pin "43") (pinfunction "VREGOUT_43") (pintype "output"))
    )
    (net (code "47") (name "P2V5") (class "Default")
      (node (ref "C216") (pin "2") (pinfunction "2_2") (pintype "passive"))
      (node (ref "C217") (pin "2") (pinfunction "2_2") (pintype "passive"))
      (node (ref "C218") (pin "2") (pinfunction "2_2") (pintype "passive"))
      (node (ref "IC17") (pin "6") (pinfunction "VCCB_6") (pintype "power_in"))
      (node (ref "IC19") (pin "6") (pinfunction "VCCB_6") (pintype "power_in"))
      (node (ref "IC20") (pin "6") (pinfunction "VCCB_6") (pintype "power_in"))
    )
    (net (code "48") (name "P3V3") (class "Default")
      (node (ref "C220") (pin "2") (pinfunction "2_2") (pintype "passive"))
      (node (ref "IC22") (pin "2") (pinfunction "VREF1_2") (pintype "input"))
      (node (ref "R209") (pin "2") (pinfunction "2_2") (pintype "passive"))
    )
    (net (code "49") (name "P3V3_USB") (class "Default")
      (node (ref "C204") (pin "2") (pinfunction "2_2") (pintype "passive"))
      (node (ref "C205") (pin "2") (pinfunction "2_2") (pintype "passive"))
      (node (ref "C213") (pin "2") (pinfunction "2_2") (pintype "passive"))
      (node (ref "C214") (pin "2") (pinfunction "2_2") (pintype "passive"))
      (node (ref "C215") (pin "2") (pinfunction "2_2") (pintype "passive"))
      (node (ref "C219") (pin "2") (pinfunction "2_2") (pintype "passive"))
      (node (ref "C221") (pin "2") (pinfunction "2_2") (pintype "passive"))
      (node (ref "C222") (pin "2") (pinfunction "2_2") (pintype "passive"))
      (node (ref "C223") (pin "2") (pinfunction "2_2") (pintype "passive"))
      (node (ref "C224") (pin "2") (pinfunction "2_2") (pintype "passive"))
      (node (ref "IC17") (pin "1") (pinfunction "DIR2_1") (pintype "input"))
      (node (ref "IC17") (pin "10") (pinfunction "DIR1_10") (pintype "input"))
      (node (ref "IC17") (pin "7") (pinfunction "VCCA_7") (pintype "power_in"))
      (node (ref "IC18") (pin "16") (pinfunction "VCCIO_16") (pintype "power_in"))
      (node (ref "IC18") (pin "36") (pinfunction "VCCIO_36") (pintype "power_in"))
      (node (ref "IC18") (pin "44") (pinfunction "VREGIN_44") (pintype "input"))
      (node (ref "IC18") (pin "50") (pinfunction "VCCIO_50") (pintype "power_in"))
      (node (ref "IC19") (pin "10") (pinfunction "DIR1_10") (pintype "input"))
      (node (ref "IC19") (pin "7") (pinfunction "VCCA_7") (pintype "power_in"))
      (node (ref "IC20") (pin "1") (pinfunction "DIR2_1") (pintype "input"))
      (node (ref "IC20") (pin "7") (pinfunction "VCCA_7") (pintype "power_in"))
      (node (ref "IC21") (pin "6") (pinfunction "ORG_6") (pintype "input"))
      (node (ref "IC21") (pin "8") (pinfunction "VCC_8") (pintype "power_in"))
      (node (ref "IC26") (pin "5") (pinfunction "OUT_5") (pintype "power_in"))
      (node (ref "J24") (pin "9") (pinfunction "9_9") (pintype "bidirectional"))
      (node (ref "L24") (pin "1") (pinfunction "1_1") (pintype "passive"))
      (node (ref "L25") (pin "1") (pinfunction "1_1") (pintype "passive"))
      (node (ref "R194") (pin "2") (pinfunction "2_2") (pintype "passive"))
      (node (ref "R195") (pin "2") (pinfunction "2_2") (pintype "passive"))
      (node (ref "R196") (pin "2") (pinfunction "2_2") (pintype "passive"))
      (node (ref "R197") (pin "2") (pinfunction "2_2") (pintype "passive"))
      (node (ref "R198") (pin "2") (pinfunction "2_2") (pintype "passive"))
      (node (ref "R202") (pin "2") (pinfunction "2_2") (pintype "passive"))
      (node (ref "R203") (pin "2") (pinfunction "2_2") (pintype "passive"))
      (node (ref "R204") (pin "2") (pinfunction "2_2") (pintype "passive"))
      (node (ref "R206") (pin "2") (pinfunction "2_2") (pintype "passive"))
      (node (ref "R207") (pin "2") (pinfunction "2_2") (pintype "passive"))
      (node (ref "R241") (pin "1") (pinfunction "1_1") (pintype "passive"))
    )
    (net (code "50") (name "unconnected-(IC18-ADBUS4-Pad17)") (class "Default")
      (node (ref "IC18") (pin "17") (pinfunction "ADBUS4_17") (pintype "bidirectional+no_connect"))
    )
    (net (code "51") (name "unconnected-(IC18-ADBUS5-Pad18)") (class "Default")
      (node (ref "IC18") (pin "18") (pinfunction "ADBUS5_18") (pintype "bidirectional+no_connect"))
    )
    (net (code "52") (name "unconnected-(IC18-ADBUS6-Pad19)") (class "Default")
      (node (ref "IC18") (pin "19") (pinfunction "ADBUS6_19") (pintype "bidirectional+no_connect"))
    )
    (net (code "53") (name "unconnected-(IC18-ADBUS7-Pad20)") (class "Default")
      (node (ref "IC18") (pin "20") (pinfunction "ADBUS7_20") (pintype "bidirectional+no_connect"))
    )
    (net (code "54") (name "unconnected-(IC18-BDBUS3-Pad25)") (class "Default")
      (node (ref "IC18") (pin "25") (pinfunction "BDBUS3_25") (pintype "bidirectional+no_connect"))
    )
    (net (code "55") (name "unconnected-(IC18-BDBUS4-Pad26)") (class "Default")
      (node (ref "IC18") (pin "26") (pinfunction "BDBUS4_26") (pintype "bidirectional+no_connect"))
    )
    (net (code "56") (name "unconnected-(IC18-BDBUS7-Pad29)") (class "Default")
      (node (ref "IC18") (pin "29") (pinfunction "BDBUS7_29") (pintype "bidirectional+no_connect"))
    )
    (net (code "57") (name "unconnected-(IC18-CDBUS2-Pad34)") (class "Default")
      (node (ref "IC18") (pin "34") (pinfunction "CDBUS2_34") (pintype "bidirectional+no_connect"))
    )
    (net (code "58") (name "unconnected-(IC18-CDBUS3-Pad35)") (class "Default")
      (node (ref "IC18") (pin "35") (pinfunction "CDBUS3_35") (pintype "bidirectional+no_connect"))
    )
    (net (code "59") (name "unconnected-(IC18-CDBUS4-Pad37)") (class "Default")
      (node (ref "IC18") (pin "37") (pinfunction "CDBUS4_37") (pintype "bidirectional"))
    )
    (net (code "60") (name "unconnected-(IC18-CDBUS5-Pad38)") (class "Default")
      (node (ref "IC18") (pin "38") (pinfunction "CDBUS5_38") (pintype "bidirectional+no_connect"))
    )
    (net (code "61") (name "unconnected-(IC18-CDBUS6-Pad39)") (class "Default")
      (node (ref "IC18") (pin "39") (pinfunction "CDBUS6_39") (pintype "bidirectional+no_connect"))
    )
    (net (code "62") (name "unconnected-(IC18-CDBUS7-Pad40)") (class "Default")
      (node (ref "IC18") (pin "40") (pinfunction "CDBUS7_40") (pintype "bidirectional+no_connect"))
    )
    (net (code "63") (name "unconnected-(IC18-~{PWREN}-Pad54)") (class "Default")
      (node (ref "IC18") (pin "54") (pinfunction "~{PWREN}_54") (pintype "output+no_connect"))
    )
    (net (code "64") (name "unconnected-(IC18-~{SUSPEND}-Pad30)") (class "Default")
      (node (ref "IC18") (pin "30") (pinfunction "~{SUSPEND}_30") (pintype "output+no_connect"))
    )
    (net (code "65") (name "unconnected-(IC21-DU-Pad7)") (class "Default")
      (node (ref "IC21") (pin "7") (pinfunction "DU_7") (pintype "passive+no_connect"))
    )
    (net (code "66") (name "unconnected-(IC26-BYP-Pad4)") (class "Default")
      (node (ref "IC26") (pin "4") (pinfunction "BYP_4") (pintype "passive+no_connect"))
    )
    (net (code "67") (name "unconnected-(J23-ID-Pad4)") (class "Default")
      (node (ref "J23") (pin "4") (pinfunction "ID_4") (pintype "passive+no_connect"))
    )
  )
)
